# ir_beacon_rev00.net
KiCad netlist of a schematic drawn in EAGLE
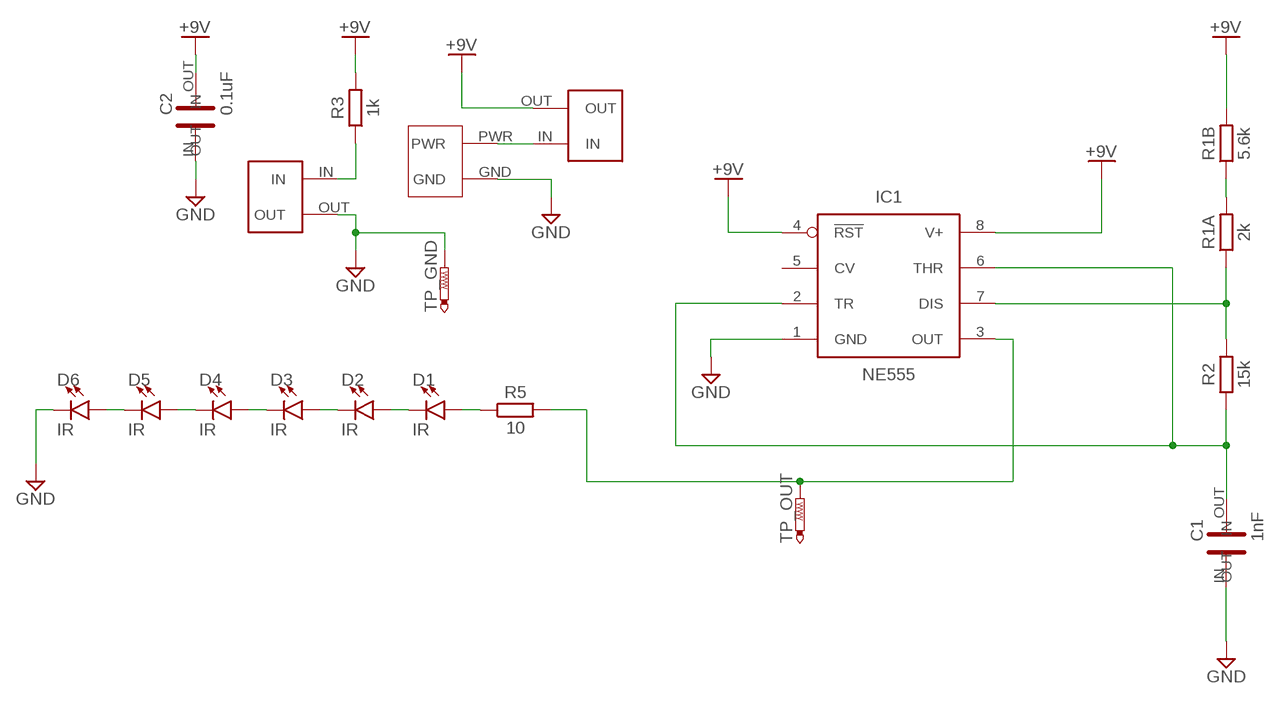
[diagram p0: schematic, sheet 1]

(export (version "E")
  (design (tool "Eeschema 10.0.6"))
  (components
    (comp (ref "BATT")
      (value "JST_THRU_HOLE")
      (footprint "eagle-import:JST_THRU_HOLE")
      (libsource (lib "eagle-import") (part "JST_THRU_HOLE"))
    )
    (comp (ref "C1")
      (value "1nF")
      (footprint "eagle-import:THRU_HOLE_CAP")
      (libsource (lib "eagle-import") (part "THRU_HOLE_CAP"))
    )
    (comp (ref "C2")
      (value "0.1uF")
      (footprint "eagle-import:THRU_HOLE_CAP")
      (libsource (lib "eagle-import") (part "THRU_HOLE_CAP"))
    )
    (comp (ref "D1")
      (value "IR")
      (footprint "eagle-import:LED_5MM")
      (libsource (lib "eagle-import") (part "LED-IRTSAL6100"))
    )
    (comp (ref "D2")
      (value "IR")
      (footprint "eagle-import:LED_5MM")
      (libsource (lib "eagle-import") (part "LED-IRTSAL6100"))
    )
    (comp (ref "D3")
      (value "IR")
      (footprint "eagle-import:LED_5MM")
      (libsource (lib "eagle-import") (part "LED-IRTSAL6100"))
    )
    (comp (ref "D4")
      (value "IR")
      (footprint "eagle-import:LED_5MM")
      (libsource (lib "eagle-import") (part "LED-IRTSAL6100"))
    )
    (comp (ref "D5")
      (value "IR")
      (footprint "eagle-import:LED_5MM")
      (libsource (lib "eagle-import") (part "LED-IRTSAL6100"))
    )
    (comp (ref "D6")
      (value "IR")
      (footprint "eagle-import:LED_5MM")
      (libsource (lib "eagle-import") (part "LED-IRTSAL6100"))
    )
    (comp (ref "IC1")
      (value "NE555")
      (footprint "eagle-import:DIP826W53P254L959H508Q8B")
      (fields
        (field (name "MANUFACTURER") "Renesas Electronics America Inc ")
        (field (name "MPN") "ICM7555IPAZ ")
      )
      (libsource (lib "eagle-import") (part "555_DIPICM7"))
    )
    (comp (ref "R1A")
      (value "2k")
      (footprint "eagle-import:RESAD1176W63L850D250B")
      (libsource (lib "eagle-import") (part "RAXIAL-11.7MM-PITCH_"))
    )
    (comp (ref "R1B")
      (value "5.6k")
      (footprint "eagle-import:RESAD1176W63L850D250B")
      (libsource (lib "eagle-import") (part "RAXIAL-11.7MM-PITCH_"))
    )
    (comp (ref "R2")
      (value "15k")
      (footprint "eagle-import:RESAD1176W63L850D250B")
      (libsource (lib "eagle-import") (part "RAXIAL-11.7MM-PITCH_"))
    )
    (comp (ref "R3")
      (value "1k")
      (footprint "eagle-import:RESAD1176W63L850D250B")
      (libsource (lib "eagle-import") (part "RAXIAL-11.7MM-PITCH_"))
    )
    (comp (ref "R5")
      (value "10")
      (footprint "eagle-import:RESAD1176W63L850D250B")
      (libsource (lib "eagle-import") (part "RAXIAL-11.7MM-PITCH_"))
    )
    (comp (ref "RED")
      (value "LED")
      (footprint "eagle-import:GEN_CONN")
      (libsource (lib "eagle-import") (part "GEN_CONN"))
    )
    (comp (ref "S1")
      (value "GEN_CONN")
      (footprint "eagle-import:GEN_CONN")
      (libsource (lib "eagle-import") (part "GEN_CONN"))
    )
    (comp (ref "TP_GND")
      (value "PTR1B2,54")
      (footprint "eagle-import:B2,54")
      (libsource (lib "eagle-import") (part "PTR1B2,54"))
    )
    (comp (ref "TP_OUT")
      (value "PTR1B2,54")
      (footprint "eagle-import:B2,54")
      (libsource (lib "eagle-import") (part "PTR1B2,54"))
    )
  )
  (nets
    (net (code "1") (name "+9V") (class "Default")
      (node (ref "C2") (pin "OUT") (pinfunction "OUT_OUT") (pintype "bidirectional"))
      (node (ref "IC1") (pin "4") (pinfunction "~{RST}_4") (pintype "input"))
      (node (ref "IC1") (pin "8") (pinfunction "V+_8") (pintype "power_in"))
      (node (ref "R1B") (pin "2") (pinfunction "2_2") (pintype "passive"))
      (node (ref "R3") (pin "2") (pinfunction "2_2") (pintype "passive"))
      (node (ref "S1") (pin "OUT") (pinfunction "OUT_OUT") (pintype "bidirectional"))
    )
    (net (code "2") (name "GND") (class "Default")
      (node (ref "BATT") (pin "GND") (pinfunction "GND_GND") (pintype "bidirectional"))
      (node (ref "C1") (pin "IN") (pinfunction "IN_IN") (pintype "bidirectional"))
      (node (ref "C2") (pin "IN") (pinfunction "IN_IN") (pintype "bidirectional"))
      (node (ref "D6") (pin "K") (pinfunction "C_K") (pintype "passive"))
      (node (ref "IC1") (pin "1") (pinfunction "GND_1") (pintype "power_in"))
      (node (ref "RED") (pin "OUT") (pinfunction "OUT_OUT") (pintype "bidirectional"))
      (node (ref "TP_GND") (pin "TP") (pinfunction "TP_TP") (pintype "input"))
    )
    (net (code "3") (name "Net-(BATT-PadPWR)") (class "Default")
      (node (ref "BATT") (pin "PWR") (pinfunction "PWR_PWR") (pintype "bidirectional"))
      (node (ref "S1") (pin "IN") (pinfunction "IN_IN") (pintype "bidirectional"))
    )
    (net (code "4") (name "Net-(D1-C)") (class "Default")
      (node (ref "D1") (pin "K") (pinfunction "C_K") (pintype "passive"))
      (node (ref "D2") (pin "A") (pinfunction "A_A") (pintype "passive"))
    )
    (net (code "5") (name "Net-(D1-PadA)") (class "Default")
      (node (ref "D1") (pin "A") (pinfunction "A_A") (pintype "passive"))
      (node (ref "R5") (pin "1") (pinfunction "1_1") (pintype "passive"))
    )
    (net (code "6") (name "Net-(D2-C)") (class "Default")
      (node (ref "D2") (pin "K") (pinfunction "C_K") (pintype "passive"))
      (node (ref "D3") (pin "A") (pinfunction "A_A") (pintype "passive"))
    )
    (net (code "7") (name "Net-(D3-C)") (class "Default")
      (node (ref "D3") (pin "K") (pinfunction "C_K") (pintype "passive"))
      (node (ref "D4") (pin "A") (pinfunction "A_A") (pintype "passive"))
    )
    (net (code "8") (name "Net-(D4-C)") (class "Default")
      (node (ref "D4") (pin "K") (pinfunction "C_K") (pintype "passive"))
      (node (ref "D5") (pin "A") (pinfunction "A_A") (pintype "passive"))
    )
    (net (code "9") (name "Net-(D5-C)") (class "Default")
      (node (ref "D5") (pin "K") (pinfunction "C_K") (pintype "passive"))
      (node (ref "D6") (pin "A") (pinfunction "A_A") (pintype "passive"))
    )
    (net (code "10") (name "Net-(IC1-DIS)") (class "Default")
      (node (ref "IC1") (pin "7") (pinfunction "DIS_7") (pintype "input"))
      (node (ref "R1A") (pin "1") (pinfunction "1_1") (pintype "passive"))
      (node (ref "R2") (pin "2") (pinfunction "2_2") (pintype "passive"))
    )
    (net (code "11") (name "Net-(IC1-OUT)") (class "Default")
      (node (ref "IC1") (pin "3") (pinfunction "OUT_3") (pintype "output"))
      (node (ref "R5") (pin "2") (pinfunction "2_2") (pintype "passive"))
      (node (ref "TP_OUT") (pin "TP") (pinfunction "TP_TP") (pintype "input"))
    )
    (net (code "12") (name "Net-(IC1-THR)") (class "Default")
      (node (ref "C1") (pin "OUT") (pinfunction "OUT_OUT") (pintype "bidirectional"))
      (node (ref "IC1") (pin "2") (pinfunction "TR_2") (pintype "input"))
      (node (ref "IC1") (pin "6") (pinfunction "THR_6") (pintype "input"))
      (node (ref "R2") (pin "1") (pinfunction "1_1") (pintype "passive"))
    )
    (net (code "13") (name "Net-(R1A-Pad2)") (class "Default")
      (node (ref "R1A") (pin "2") (pinfunction "2_2") (pintype "passive"))
      (node (ref "R1B") (pin "1") (pinfunction "1_1") (pintype "passive"))
    )
    (net (code "14") (name "Net-(R3-Pad1)") (class "Default")
      (node (ref "R3") (pin "1") (pinfunction "1_1") (pintype "passive"))
      (node (ref "RED") (pin "IN") (pinfunction "IN_IN") (pintype "bidirectional"))
    )
    (net (code "15") (name "unconnected-(IC1-CV-Pad5)") (class "Default")
      (node (ref "IC1") (pin "5") (pinfunction "CV_5") (pintype "input"))
    )
  )
)
